# servo_driver.net
KiCad netlist of a schematic drawn in EAGLE
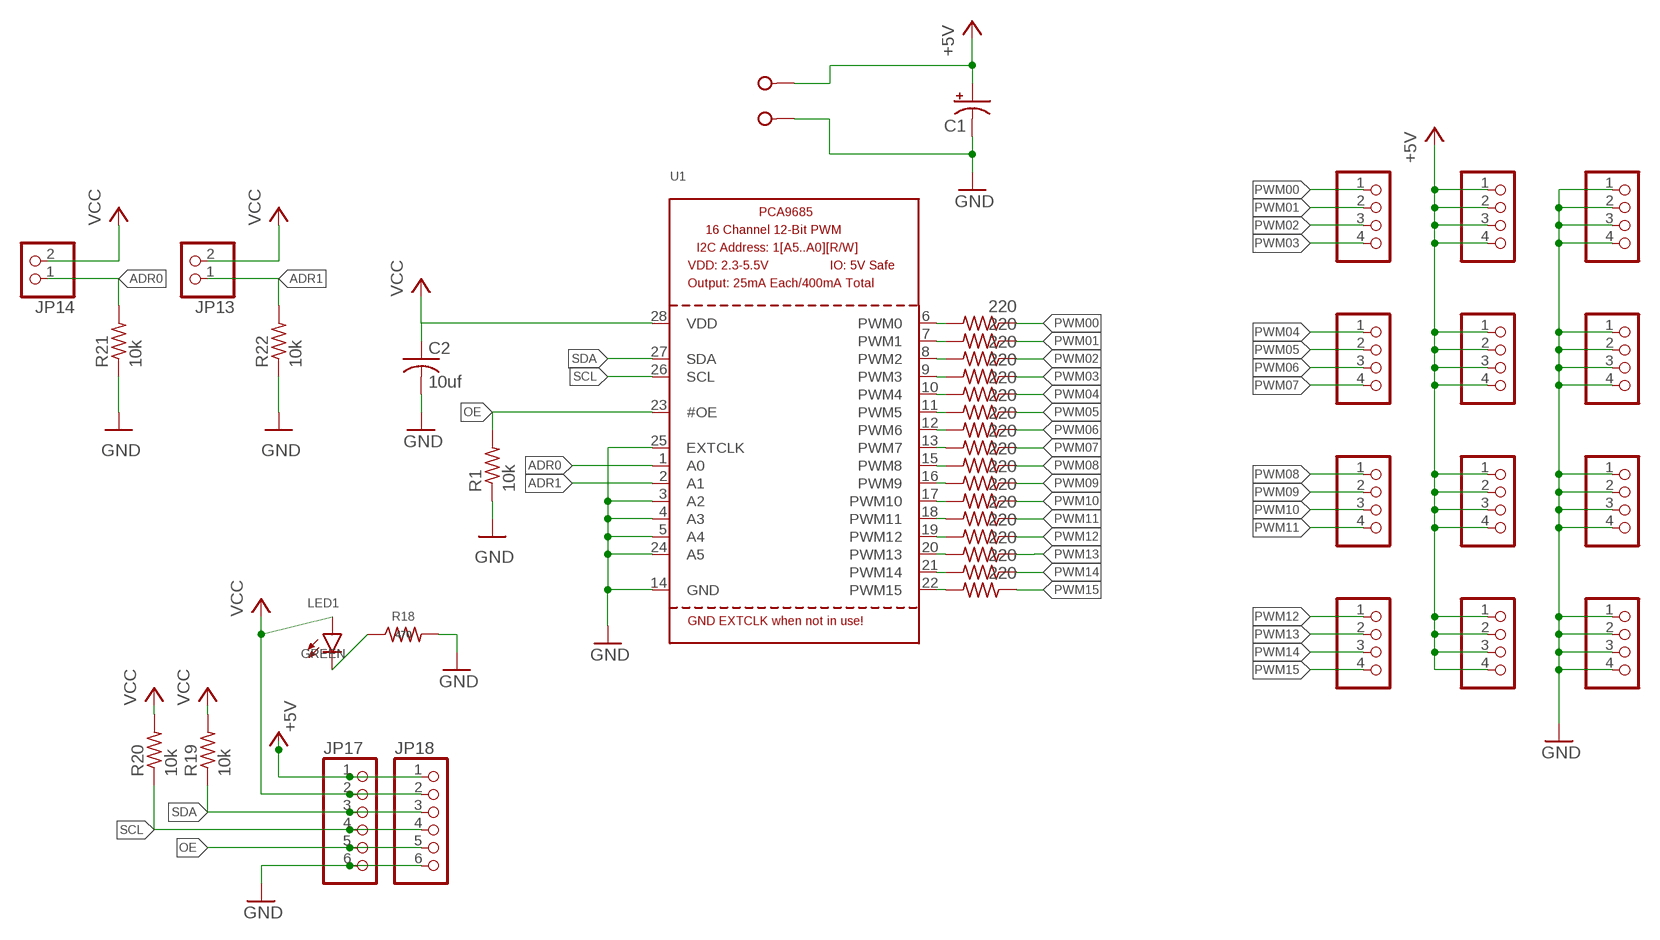
[diagram p0: schematic, sheet 1]

(export (version "E")
  (design (tool "Eeschema 10.0.6"))
  (components
    (comp (ref "C1")
      (value "CPOL-USE5-8.5")
      (footprint "eagle-import:E5-8,5")
      (libsource (lib "eagle-import") (part "CPOL-USE5-8.5"))
    )
    (comp (ref "C2")
      (value "10uf")
      (footprint "eagle-import:C025-024X044")
      (libsource (lib "eagle-import") (part "C-US025-024X044"))
    )
    (comp (ref "JP1")
      (value "PINHD-1X4")
      (footprint "eagle-import:1X04")
      (libsource (lib "eagle-import") (part "PINHD-1X4"))
    )
    (comp (ref "JP2")
      (value "PINHD-1X4")
      (footprint "eagle-import:1X04")
      (libsource (lib "eagle-import") (part "PINHD-1X4"))
    )
    (comp (ref "JP3")
      (value "PINHD-1X4")
      (footprint "eagle-import:1X04")
      (libsource (lib "eagle-import") (part "PINHD-1X4"))
    )
    (comp (ref "JP4")
      (value "PINHD-1X4")
      (footprint "eagle-import:1X04")
      (libsource (lib "eagle-import") (part "PINHD-1X4"))
    )
    (comp (ref "JP5")
      (value "PINHD-1X4")
      (footprint "eagle-import:1X04")
      (libsource (lib "eagle-import") (part "PINHD-1X4"))
    )
    (comp (ref "JP6")
      (value "PINHD-1X4")
      (footprint "eagle-import:1X04")
      (libsource (lib "eagle-import") (part "PINHD-1X4"))
    )
    (comp (ref "JP7")
      (value "PINHD-1X4")
      (footprint "eagle-import:1X04")
      (libsource (lib "eagle-import") (part "PINHD-1X4"))
    )
    (comp (ref "JP8")
      (value "PINHD-1X4")
      (footprint "eagle-import:1X04")
      (libsource (lib "eagle-import") (part "PINHD-1X4"))
    )
    (comp (ref "JP9")
      (value "PINHD-1X4")
      (footprint "eagle-import:1X04")
      (libsource (lib "eagle-import") (part "PINHD-1X4"))
    )
    (comp (ref "JP10")
      (value "PINHD-1X4")
      (footprint "eagle-import:1X04")
      (libsource (lib "eagle-import") (part "PINHD-1X4"))
    )
    (comp (ref "JP11")
      (value "PINHD-1X4")
      (footprint "eagle-import:1X04")
      (libsource (lib "eagle-import") (part "PINHD-1X4"))
    )
    (comp (ref "JP12")
      (value "PINHD-1X4")
      (footprint "eagle-import:1X04")
      (libsource (lib "eagle-import") (part "PINHD-1X4"))
    )
    (comp (ref "JP13")
      (value "PINHD-1X2")
      (footprint "eagle-import:1X02")
      (libsource (lib "eagle-import") (part "PINHD-1X2"))
    )
    (comp (ref "JP14")
      (value "PINHD-1X2")
      (footprint "eagle-import:1X02")
      (libsource (lib "eagle-import") (part "PINHD-1X2"))
    )
    (comp (ref "JP17")
      (value "PINHD-1X6CB")
      (footprint "eagle-import:1X06-CLEANBIG")
      (libsource (lib "eagle-import") (part "PINHD-1X6CB"))
    )
    (comp (ref "JP18")
      (value "PINHD-1X6CB")
      (footprint "eagle-import:1X06-CLEANBIG")
      (libsource (lib "eagle-import") (part "PINHD-1X6CB"))
    )
    (comp (ref "LED1")
      (value "GREEN")
      (footprint "eagle-import:LED3MM")
      (libsource (lib "eagle-import") (part "LED3MM"))
    )
    (comp (ref "R1")
      (value "10k")
      (footprint "eagle-import:0207_10")
      (libsource (lib "eagle-import") (part "R-US_0207/10"))
    )
    (comp (ref "R2")
      (value "220")
      (footprint "eagle-import:0207_10")
      (libsource (lib "eagle-import") (part "R-US_0207/10"))
    )
    (comp (ref "R3")
      (value "220")
      (footprint "eagle-import:0207_10")
      (libsource (lib "eagle-import") (part "R-US_0207/10"))
    )
    (comp (ref "R4")
      (value "220")
      (footprint "eagle-import:0207_10")
      (libsource (lib "eagle-import") (part "R-US_0207/10"))
    )
    (comp (ref "R5")
      (value "220")
      (footprint "eagle-import:0207_10")
      (libsource (lib "eagle-import") (part "R-US_0207/10"))
    )
    (comp (ref "R6")
      (value "220")
      (footprint "eagle-import:0207_10")
      (libsource (lib "eagle-import") (part "R-US_0207/10"))
    )
    (comp (ref "R7")
      (value "220")
      (footprint "eagle-import:0207_10")
      (libsource (lib "eagle-import") (part "R-US_0207/10"))
    )
    (comp (ref "R8")
      (value "220")
      (footprint "eagle-import:0207_10")
      (libsource (lib "eagle-import") (part "R-US_0207/10"))
    )
    (comp (ref "R9")
      (value "220")
      (footprint "eagle-import:0207_10")
      (libsource (lib "eagle-import") (part "R-US_0207/10"))
    )
    (comp (ref "R10")
      (value "220")
      (footprint "eagle-import:0207_10")
      (libsource (lib "eagle-import") (part "R-US_0207/10"))
    )
    (comp (ref "R11")
      (value "220")
      (footprint "eagle-import:0207_10")
      (libsource (lib "eagle-import") (part "R-US_0207/10"))
    )
    (comp (ref "R12")
      (value "220")
      (footprint "eagle-import:0207_10")
      (libsource (lib "eagle-import") (part "R-US_0207/10"))
    )
    (comp (ref "R13")
      (value "220")
      (footprint "eagle-import:0207_10")
      (libsource (lib "eagle-import") (part "R-US_0207/10"))
    )
    (comp (ref "R14")
      (value "220")
      (footprint "eagle-import:0207_10")
      (libsource (lib "eagle-import") (part "R-US_0207/10"))
    )
    (comp (ref "R15")
      (value "220")
      (footprint "eagle-import:0207_10")
      (libsource (lib "eagle-import") (part "R-US_0207/10"))
    )
    (comp (ref "R16")
      (value "220")
      (footprint "eagle-import:0207_10")
      (libsource (lib "eagle-import") (part "R-US_0207/10"))
    )
    (comp (ref "R17")
      (value "220")
      (footprint "eagle-import:0207_10")
      (libsource (lib "eagle-import") (part "R-US_0207/10"))
    )
    (comp (ref "R18")
      (value "470")
      (footprint "eagle-import:0207_10")
      (libsource (lib "eagle-import") (part "R-US_0207/10"))
    )
    (comp (ref "R19")
      (value "10k")
      (footprint "eagle-import:0207_10")
      (libsource (lib "eagle-import") (part "R-US_0207/10"))
    )
    (comp (ref "R20")
      (value "10k")
      (footprint "eagle-import:0207_10")
      (libsource (lib "eagle-import") (part "R-US_0207/10"))
    )
    (comp (ref "R21")
      (value "10k")
      (footprint "eagle-import:0207_10")
      (libsource (lib "eagle-import") (part "R-US_0207/10"))
    )
    (comp (ref "R22")
      (value "10k")
      (footprint "eagle-import:0207_10")
      (libsource (lib "eagle-import") (part "R-US_0207/10"))
    )
    (comp (ref "U1")
      (value "PCA9685")
      (footprint "eagle-import:TSSOP28")
      (libsource (lib "eagle-import") (part "PCA9685"))
    )
    (comp (ref "X1")
      (value "W237-02P")
      (footprint "eagle-import:W237-132")
      (libsource (lib "eagle-import") (part "W237-02P"))
    )
  )
  (nets
    (net (code "1") (name "+5V") (class "Default")
      (node (ref "C1") (pin "+") (pinfunction "+_+") (pintype "passive"))
      (node (ref "JP17") (pin "1") (pinfunction "1_1") (pintype "passive"))
      (node (ref "JP18") (pin "1") (pinfunction "1_1") (pintype "passive"))
      (node (ref "JP5") (pin "1") (pinfunction "1_1") (pintype "passive"))
      (node (ref "JP5") (pin "2") (pinfunction "2_2") (pintype "passive"))
      (node (ref "JP5") (pin "3") (pinfunction "3_3") (pintype "passive"))
      (node (ref "JP5") (pin "4") (pinfunction "4_4") (pintype "passive"))
      (node (ref "JP6") (pin "1") (pinfunction "1_1") (pintype "passive"))
      (node (ref "JP6") (pin "2") (pinfunction "2_2") (pintype "passive"))
      (node (ref "JP6") (pin "3") (pinfunction "3_3") (pintype "passive"))
      (node (ref "JP6") (pin "4") (pinfunction "4_4") (pintype "passive"))
      (node (ref "JP7") (pin "1") (pinfunction "1_1") (pintype "passive"))
      (node (ref "JP7") (pin "2") (pinfunction "2_2") (pintype "passive"))
      (node (ref "JP7") (pin "3") (pinfunction "3_3") (pintype "passive"))
      (node (ref "JP7") (pin "4") (pinfunction "4_4") (pintype "passive"))
      (node (ref "JP8") (pin "1") (pinfunction "1_1") (pintype "passive"))
      (node (ref "JP8") (pin "2") (pinfunction "2_2") (pintype "passive"))
      (node (ref "JP8") (pin "3") (pinfunction "3_3") (pintype "passive"))
      (node (ref "JP8") (pin "4") (pinfunction "4_4") (pintype "passive"))
      (node (ref "X1") (pin "1") (pinfunction "KL_1") (pintype "passive"))
    )
    (net (code "2") (name "ADR0") (class "Default")
      (node (ref "JP14") (pin "1") (pinfunction "1_1") (pintype "passive"))
      (node (ref "R21") (pin "2") (pinfunction "2_2") (pintype "passive"))
      (node (ref "U1") (pin "1") (pinfunction "A0_1") (pintype "bidirectional"))
    )
    (net (code "3") (name "ADR1") (class "Default")
      (node (ref "JP13") (pin "1") (pinfunction "1_1") (pintype "passive"))
      (node (ref "R22") (pin "2") (pinfunction "2_2") (pintype "passive"))
      (node (ref "U1") (pin "2") (pinfunction "A1_2") (pintype "bidirectional"))
    )
    (net (code "4") (name "GND") (class "Default")
      (node (ref "C1") (pin "-") (pinfunction "-_-") (pintype "passive"))
      (node (ref "C2") (pin "2") (pinfunction "2_2") (pintype "passive"))
      (node (ref "JP10") (pin "1") (pinfunction "1_1") (pintype "passive"))
      (node (ref "JP10") (pin "2") (pinfunction "2_2") (pintype "passive"))
      (node (ref "JP10") (pin "3") (pinfunction "3_3") (pintype "passive"))
      (node (ref "JP10") (pin "4") (pinfunction "4_4") (pintype "passive"))
      (node (ref "JP11") (pin "1") (pinfunction "1_1") (pintype "passive"))
      (node (ref "JP11") (pin "2") (pinfunction "2_2") (pintype "passive"))
      (node (ref "JP11") (pin "3") (pinfunction "3_3") (pintype "passive"))
      (node (ref "JP11") (pin "4") (pinfunction "4_4") (pintype "passive"))
      (node (ref "JP12") (pin "1") (pinfunction "1_1") (pintype "passive"))
      (node (ref "JP12") (pin "2") (pinfunction "2_2") (pintype "passive"))
      (node (ref "JP12") (pin "3") (pinfunction "3_3") (pintype "passive"))
      (node (ref "JP12") (pin "4") (pinfunction "4_4") (pintype "passive"))
      (node (ref "JP17") (pin "6") (pinfunction "6_6") (pintype "passive"))
      (node (ref "JP18") (pin "6") (pinfunction "6_6") (pintype "passive"))
      (node (ref "JP9") (pin "1") (pinfunction "1_1") (pintype "passive"))
      (node (ref "JP9") (pin "2") (pinfunction "2_2") (pintype "passive"))
      (node (ref "JP9") (pin "3") (pinfunction "3_3") (pintype "passive"))
      (node (ref "JP9") (pin "4") (pinfunction "4_4") (pintype "passive"))
      (node (ref "R1") (pin "1") (pinfunction "1_1") (pintype "passive"))
      (node (ref "R18") (pin "2") (pinfunction "2_2") (pintype "passive"))
      (node (ref "R21") (pin "1") (pinfunction "1_1") (pintype "passive"))
      (node (ref "R22") (pin "1") (pinfunction "1_1") (pintype "passive"))
      (node (ref "U1") (pin "14") (pinfunction "GND_14") (pintype "power_in"))
      (node (ref "U1") (pin "24") (pinfunction "A5_24") (pintype "bidirectional"))
      (node (ref "U1") (pin "25") (pinfunction "EXTCLK_25") (pintype "input"))
      (node (ref "U1") (pin "3") (pinfunction "A2_3") (pintype "bidirectional"))
      (node (ref "U1") (pin "4") (pinfunction "A3_4") (pintype "bidirectional"))
      (node (ref "U1") (pin "5") (pinfunction "A4_5") (pintype "bidirectional"))
      (node (ref "X1") (pin "2") (pinfunction "KL_2") (pintype "passive"))
    )
    (net (code "5") (name "Net-(LED1-C)") (class "Default")
      (node (ref "LED1") (pin "K") (pinfunction "C_K") (pintype "passive"))
      (node (ref "R18") (pin "1") (pinfunction "1_1") (pintype "passive"))
    )
    (net (code "6") (name "Net-(U1-PWM0)") (class "Default")
      (node (ref "R2") (pin "2") (pinfunction "2_2") (pintype "passive"))
      (node (ref "U1") (pin "6") (pinfunction "PWM0_6") (pintype "output"))
    )
    (net (code "7") (name "Net-(U1-PWM1)") (class "Default")
      (node (ref "R3") (pin "2") (pinfunction "2_2") (pintype "passive"))
      (node (ref "U1") (pin "7") (pinfunction "PWM1_7") (pintype "output"))
    )
    (net (code "8") (name "Net-(U1-PWM2)") (class "Default")
      (node (ref "R4") (pin "2") (pinfunction "2_2") (pintype "passive"))
      (node (ref "U1") (pin "8") (pinfunction "PWM2_8") (pintype "output"))
    )
    (net (code "9") (name "Net-(U1-PWM3)") (class "Default")
      (node (ref "R5") (pin "2") (pinfunction "2_2") (pintype "passive"))
      (node (ref "U1") (pin "9") (pinfunction "PWM3_9") (pintype "output"))
    )
    (net (code "10") (name "Net-(U1-PWM4)") (class "Default")
      (node (ref "R6") (pin "2") (pinfunction "2_2") (pintype "passive"))
      (node (ref "U1") (pin "10") (pinfunction "PWM4_10") (pintype "output"))
    )
    (net (code "11") (name "Net-(U1-PWM5)") (class "Default")
      (node (ref "R7") (pin "2") (pinfunction "2_2") (pintype "passive"))
      (node (ref "U1") (pin "11") (pinfunction "PWM5_11") (pintype "output"))
    )
    (net (code "12") (name "Net-(U1-PWM6)") (class "Default")
      (node (ref "R8") (pin "2") (pinfunction "2_2") (pintype "passive"))
      (node (ref "U1") (pin "12") (pinfunction "PWM6_12") (pintype "output"))
    )
    (net (code "13") (name "Net-(U1-PWM7)") (class "Default")
      (node (ref "R9") (pin "2") (pinfunction "2_2") (pintype "passive"))
      (node (ref "U1") (pin "13") (pinfunction "PWM7_13") (pintype "output"))
    )
    (net (code "14") (name "Net-(U1-PWM8)") (class "Default")
      (node (ref "R10") (pin "2") (pinfunction "2_2") (pintype "passive"))
      (node (ref "U1") (pin "15") (pinfunction "PWM8_15") (pintype "output"))
    )
    (net (code "15") (name "Net-(U1-PWM9)") (class "Default")
      (node (ref "R11") (pin "2") (pinfunction "2_2") (pintype "passive"))
      (node (ref "U1") (pin "16") (pinfunction "PWM9_16") (pintype "output"))
    )
    (net (code "16") (name "Net-(U1-PWM10)") (class "Default")
      (node (ref "R12") (pin "2") (pinfunction "2_2") (pintype "passive"))
      (node (ref "U1") (pin "17") (pinfunction "PWM10_17") (pintype "output"))
    )
    (net (code "17") (name "Net-(U1-PWM11)") (class "Default")
      (node (ref "R13") (pin "2") (pinfunction "2_2") (pintype "passive"))
      (node (ref "U1") (pin "18") (pinfunction "PWM11_18") (pintype "output"))
    )
    (net (code "18") (name "Net-(U1-PWM12)") (class "Default")
      (node (ref "R14") (pin "2") (pinfunction "2_2") (pintype "passive"))
      (node (ref "U1") (pin "19") (pinfunction "PWM12_19") (pintype "output"))
    )
    (net (code "19") (name "Net-(U1-PWM13)") (class "Default")
      (node (ref "R15") (pin "2") (pinfunction "2_2") (pintype "passive"))
      (node (ref "U1") (pin "20") (pinfunction "PWM13_20") (pintype "output"))
    )
    (net (code "20") (name "Net-(U1-PWM14)") (class "Default")
      (node (ref "R16") (pin "2") (pinfunction "2_2") (pintype "passive"))
      (node (ref "U1") (pin "21") (pinfunction "PWM14_21") (pintype "output"))
    )
    (net (code "21") (name "Net-(U1-PWM15)") (class "Default")
      (node (ref "R17") (pin "2") (pinfunction "2_2") (pintype "passive"))
      (node (ref "U1") (pin "22") (pinfunction "PWM15_22") (pintype "output"))
    )
    (net (code "22") (name "OE") (class "Default")
      (node (ref "JP17") (pin "5") (pinfunction "5_5") (pintype "passive"))
      (node (ref "JP18") (pin "5") (pinfunction "5_5") (pintype "passive"))
      (node (ref "R1") (pin "2") (pinfunction "2_2") (pintype "passive"))
      (node (ref "U1") (pin "23") (pinfunction "#OE_23") (pintype "input"))
    )
    (net (code "23") (name "PWM00") (class "Default")
      (node (ref "JP1") (pin "1") (pinfunction "1_1") (pintype "passive"))
      (node (ref "R2") (pin "1") (pinfunction "1_1") (pintype "passive"))
    )
    (net (code "24") (name "PWM01") (class "Default")
      (node (ref "JP1") (pin "2") (pinfunction "2_2") (pintype "passive"))
      (node (ref "R3") (pin "1") (pinfunction "1_1") (pintype "passive"))
    )
    (net (code "25") (name "PWM02") (class "Default")
      (node (ref "JP1") (pin "3") (pinfunction "3_3") (pintype "passive"))
      (node (ref "R4") (pin "1") (pinfunction "1_1") (pintype "passive"))
    )
    (net (code "26") (name "PWM03") (class "Default")
      (node (ref "JP1") (pin "4") (pinfunction "4_4") (pintype "passive"))
      (node (ref "R5") (pin "1") (pinfunction "1_1") (pintype "passive"))
    )
    (net (code "27") (name "PWM04") (class "Default")
      (node (ref "JP2") (pin "1") (pinfunction "1_1") (pintype "passive"))
      (node (ref "R6") (pin "1") (pinfunction "1_1") (pintype "passive"))
    )
    (net (code "28") (name "PWM05") (class "Default")
      (node (ref "JP2") (pin "2") (pinfunction "2_2") (pintype "passive"))
      (node (ref "R7") (pin "1") (pinfunction "1_1") (pintype "passive"))
    )
    (net (code "29") (name "PWM06") (class "Default")
      (node (ref "JP2") (pin "3") (pinfunction "3_3") (pintype "passive"))
      (node (ref "R8") (pin "1") (pinfunction "1_1") (pintype "passive"))
    )
    (net (code "30") (name "PWM07") (class "Default")
      (node (ref "JP2") (pin "4") (pinfunction "4_4") (pintype "passive"))
      (node (ref "R9") (pin "1") (pinfunction "1_1") (pintype "passive"))
    )
    (net (code "31") (name "PWM08") (class "Default")
      (node (ref "JP3") (pin "1") (pinfunction "1_1") (pintype "passive"))
      (node (ref "R10") (pin "1") (pinfunction "1_1") (pintype "passive"))
    )
    (net (code "32") (name "PWM09") (class "Default")
      (node (ref "JP3") (pin "2") (pinfunction "2_2") (pintype "passive"))
      (node (ref "R11") (pin "1") (pinfunction "1_1") (pintype "passive"))
    )
    (net (code "33") (name "PWM10") (class "Default")
      (node (ref "JP3") (pin "3") (pinfunction "3_3") (pintype "passive"))
      (node (ref "R12") (pin "1") (pinfunction "1_1") (pintype "passive"))
    )
    (net (code "34") (name "PWM11") (class "Default")
      (node (ref "JP3") (pin "4") (pinfunction "4_4") (pintype "passive"))
      (node (ref "R13") (pin "1") (pinfunction "1_1") (pintype "passive"))
    )
    (net (code "35") (name "PWM12") (class "Default")
      (node (ref "JP4") (pin "1") (pinfunction "1_1") (pintype "passive"))
      (node (ref "R14") (pin "1") (pinfunction "1_1") (pintype "passive"))
    )
    (net (code "36") (name "PWM13") (class "Default")
      (node (ref "JP4") (pin "2") (pinfunction "2_2") (pintype "passive"))
      (node (ref "R15") (pin "1") (pinfunction "1_1") (pintype "passive"))
    )
    (net (code "37") (name "PWM14") (class "Default")
      (node (ref "JP4") (pin "3") (pinfunction "3_3") (pintype "passive"))
      (node (ref "R16") (pin "1") (pinfunction "1_1") (pintype "passive"))
    )
    (net (code "38") (name "PWM15") (class "Default")
      (node (ref "JP4") (pin "4") (pinfunction "4_4") (pintype "passive"))
      (node (ref "R17") (pin "1") (pinfunction "1_1") (pintype "passive"))
    )
    (net (code "39") (name "SCL") (class "Default")
      (node (ref "JP17") (pin "4") (pinfunction "4_4") (pintype "passive"))
      (node (ref "JP18") (pin "4") (pinfunction "4_4") (pintype "passive"))
      (node (ref "R20") (pin "1") (pinfunction "1_1") (pintype "passive"))
      (node (ref "U1") (pin "26") (pinfunction "SCL_26") (pintype "bidirectional"))
    )
    (net (code "40") (name "SDA") (class "Default")
      (node (ref "JP17") (pin "3") (pinfunction "3_3") (pintype "passive"))
      (node (ref "JP18") (pin "3") (pinfunction "3_3") (pintype "passive"))
      (node (ref "R19") (pin "1") (pinfunction "1_1") (pintype "passive"))
      (node (ref "U1") (pin "27") (pinfunction "SDA_27") (pintype "bidirectional"))
    )
    (net (code "41") (name "VCC") (class "Default")
      (node (ref "C2") (pin "1") (pinfunction "1_1") (pintype "passive"))
      (node (ref "JP13") (pin "2") (pinfunction "2_2") (pintype "passive"))
      (node (ref "JP14") (pin "2") (pinfunction "2_2") (pintype "passive"))
      (node (ref "JP17") (pin "2") (pinfunction "2_2") (pintype "passive"))
      (node (ref "JP18") (pin "2") (pinfunction "2_2") (pintype "passive"))
      (node (ref "LED1") (pin "A") (pinfunction "A_A") (pintype "passive"))
      (node (ref "R19") (pin "2") (pinfunction "2_2") (pintype "passive"))
      (node (ref "R20") (pin "2") (pinfunction "2_2") (pintype "passive"))
      (node (ref "U1") (pin "28") (pinfunction "VDD_28") (pintype "power_in"))
    )
  )
)
